# SSFocuser-B-DRV8825.net
KiCad netlist of a schematic drawn in Altium Designer
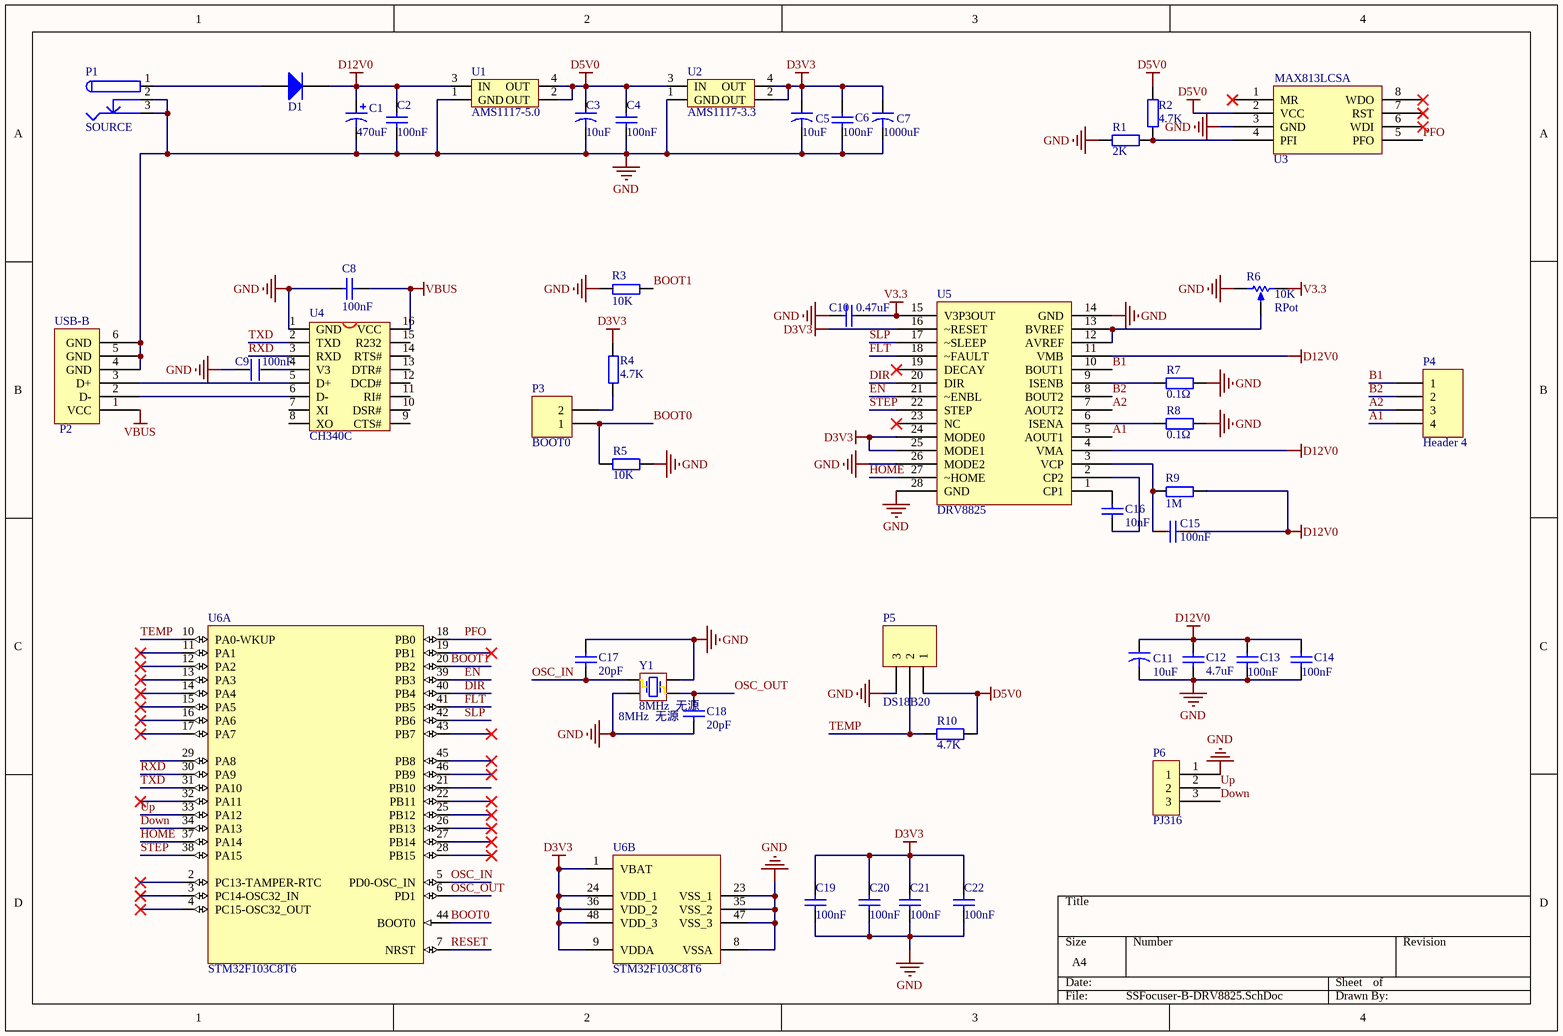
[diagram p0: SSFocuser-B-DRV8825.SchDoc]

(export (version "E")
  (design (tool "Eeschema 10.0.6"))
  (components
    (comp (ref "C1")
      (value "470uF")
      (footprint "16V/470U(CD10X10D5)")
      (description "470UF      16V      CD10X10D5")
      (libsource (lib "平台原理图symbol图库V1.0") (part "C470UF016S"))
    )
    (comp (ref "C2")
      (value "100nF")
      (footprint "0603C")
      (description "Capacitor")
      (fields (field (name "PUBLISHER") "Altium Limited"))
      (libsource (lib "Crazy_PCB") (part "Cap"))
    )
    (comp (ref "C3")
      (value "10uF")
      (footprint "3216")
      (fields (field (name "VAULE") "10uF"))
      (libsource (lib "Crazy_PCB") (part "CAP2"))
    )
    (comp (ref "C4")
      (value "100nF")
      (footprint "0603C")
      (description "Capacitor")
      (fields (field (name "PUBLISHER") "Altium Limited"))
      (libsource (lib "Crazy_PCB") (part "Cap"))
    )
    (comp (ref "C5")
      (value "10uF")
      (footprint "3216")
      (fields (field (name "VAULE") "10uF"))
      (libsource (lib "Crazy_PCB") (part "CAP2"))
    )
    (comp (ref "C6")
      (value "100nF")
      (footprint "0603C")
      (description "Capacitor")
      (fields (field (name "PUBLISHER") "Altium Limited"))
      (libsource (lib "Crazy_PCB") (part "Cap"))
    )
    (comp (ref "C7")
      (value "1000uF")
      (footprint "16V/470U(CD10X10D5)")
      (fields (field (name "VAULE") "1000uF"))
      (libsource (lib "Crazy_PCB") (part "CAP2"))
    )
    (comp (ref "C8")
      (value "100nF")
      (footprint "0603C")
      (description "Capacitor")
      (fields (field (name "PUBLISHER") "Altium Limited"))
      (libsource (lib "Crazy_PCB") (part "Cap"))
    )
    (comp (ref "C9")
      (value "100nF")
      (footprint "0603C")
      (libsource (lib "WarShip V3 STM32103封装库") (part "C"))
    )
    (comp (ref "C10")
      (value "0.47uF")
      (footprint "0603C")
      (description "Capacitor")
      (fields (field (name "PUBLISHER") "Altium Limited"))
      (libsource (lib "Crazy_PCB") (part "Cap"))
    )
    (comp (ref "C11")
      (value "10uF")
      (footprint "3216")
      (fields (field (name "VAULE") "10uF"))
      (libsource (lib "Crazy_PCB") (part "CAP2"))
    )
    (comp (ref "C12")
      (value "4.7uF")
      (footprint "1206C")
      (description "Capacitor")
      (fields (field (name "PUBLISHER") "Altium Limited"))
      (libsource (lib "Crazy_PCB") (part "Cap"))
    )
    (comp (ref "C13")
      (value "100nF")
      (footprint "0603C")
      (description "Capacitor")
      (fields (field (name "PUBLISHER") "Altium Limited"))
      (libsource (lib "Crazy_PCB") (part "Cap"))
    )
    (comp (ref "C14")
      (value "100nF")
      (footprint "0603C")
      (description "Capacitor")
      (fields (field (name "PUBLISHER") "Altium Limited"))
      (libsource (lib "Crazy_PCB") (part "Cap"))
    )
    (comp (ref "C15")
      (value "100nF")
      (footprint "0603C")
      (description "Capacitor")
      (fields (field (name "PUBLISHER") "Altium Limited"))
      (libsource (lib "Crazy_PCB") (part "Cap"))
    )
    (comp (ref "C16")
      (value "10nF")
      (footprint "0603C")
      (description "Capacitor")
      (fields (field (name "PUBLISHER") "Altium Limited"))
      (libsource (lib "Crazy_PCB") (part "Cap"))
    )
    (comp (ref "C17")
      (value "20pF")
      (footprint "0603C")
      (description "Capacitor")
      (fields (field (name "PUBLISHER") "Altium Limited"))
      (libsource (lib "JL_SCH") (part "Cap"))
    )
    (comp (ref "C18")
      (value "20pF")
      (footprint "0603C")
      (description "Capacitor")
      (fields (field (name "PUBLISHER") "Altium Limited"))
      (libsource (lib "JL_SCH") (part "Cap"))
    )
    (comp (ref "C19")
      (value "100nF")
      (footprint "0603C")
      (description "Capacitor")
      (fields (field (name "PUBLISHER") "Altium Limited"))
      (libsource (lib "Crazy_PCB") (part "Cap"))
    )
    (comp (ref "C20")
      (value "100nF")
      (footprint "0603C")
      (description "Capacitor")
      (fields (field (name "PUBLISHER") "Altium Limited"))
      (libsource (lib "Crazy_PCB") (part "Cap"))
    )
    (comp (ref "C21")
      (value "100nF")
      (footprint "0603C")
      (description "Capacitor")
      (fields (field (name "PUBLISHER") "Altium Limited"))
      (libsource (lib "Crazy_PCB") (part "Cap"))
    )
    (comp (ref "C22")
      (value "100nF")
      (footprint "0603C")
      (description "Capacitor")
      (fields (field (name "PUBLISHER") "Altium Limited"))
      (libsource (lib "Crazy_PCB") (part "Cap"))
    )
    (comp (ref "D1")
      (value "M7")
      (footprint "DO-214AC")
      (description "High Conductance Fast Diode")
      (fields (field (name "PUBLISHER") "Altium Limited"))
      (libsource (lib "Crazy_PCB") (part "Diode"))
    )
    (comp (ref "P1")
      (value "SOURCE")
      (footprint "DC_5.5MM")
      (fields (field (name "PUBLISHER") "Altium Limited"))
      (libsource (lib "Crazy_PCB") (part "SOURCE"))
    )
    (comp (ref "P2") (value "USB-B") (footprint "USB-B") (libsource (lib "DX") (part "USB-B")))
    (comp (ref "P3")
      (value "BOOT0")
      (footprint "HDR1X2")
      (description "Header, 2-Pin")
      (fields (field (name "PUBLISHER") "Altium Limited"))
      (libsource (lib "Miscellaneous Connectors") (part "MHDR1X2"))
    )
    (comp (ref "P4")
      (value "Header 4")
      (footprint "XH_4_V")
      (description "Header, 4-Pin")
      (fields (field (name "PUBLISHER") "Altium Limited"))
      (libsource (lib "Miscellaneous Connectors") (part "Header 4"))
    )
    (comp (ref "P5")
      (value "DS18B20")
      (footprint "TO-92B")
      (description "Header, 3-Pin")
      (fields (field (name "PUBLISHER") "Altium Limited"))
      (libsource (lib "Miscellaneous Connectors") (part "Header 3"))
    )
    (comp (ref "P6") (value "PJ316") (footprint "PJ316") (libsource (lib "SS") (part "PJ316")))
    (comp (ref "R1")
      (value "2K")
      (footprint "0603R")
      (description "Resistor")
      (fields (field (name "PUBLISHER") "Altium Limited"))
      (libsource (lib "Crazy_PCB") (part "RES"))
    )
    (comp (ref "R2")
      (value "4.7K")
      (footprint "0603R")
      (description "Resistor")
      (fields (field (name "PUBLISHER") "Altium Limited"))
      (libsource (lib "") (part "RES_2"))
    )
    (comp (ref "R3") (value "10K") (footprint "0603R") (libsource (lib "WarShip V3 STM32103封装库") (part "R")))
    (comp (ref "R4") (value "4.7K") (footprint "0603R") (libsource (lib "WarShip V3 STM32103封装库") (part "R")))
    (comp (ref "R5")
      (value "10K")
      (footprint "0603R")
      (description "Resistor")
      (fields (field (name "PUBLISHER") "Altium Limited"))
      (libsource (lib "") (part "RES_1"))
    )
    (comp (ref "R6")
      (value "RPot")
      (footprint "VR_SMD")
      (description "Potentiometer")
      (fields (field (name "ALTIUM_VALUE") "10K") (field (name "PUBLISHER") "Altium Limited"))
      (libsource (lib "Miscellaneous Devices") (part "RPot"))
    )
    (comp (ref "R7")
      (value "0.1Ω")
      (footprint "1206R")
      (description "Resistor")
      (fields (field (name "PUBLISHER") "Altium Limited"))
      (libsource (lib "Crazy_PCB") (part "RES"))
    )
    (comp (ref "R8")
      (value "0.1Ω")
      (footprint "1206R")
      (description "Resistor")
      (fields (field (name "PUBLISHER") "Altium Limited"))
      (libsource (lib "Crazy_PCB") (part "RES"))
    )
    (comp (ref "R9") (value "1M") (footprint "0603R") (libsource (lib "WarShip V3 STM32103封装库") (part "R")))
    (comp (ref "R10")
      (value "4.7K")
      (footprint "0603R")
      (description "Resistor")
      (fields (field (name "PUBLISHER") "Altium Limited"))
      (libsource (lib "") (part "RES_1"))
    )
    (comp (ref "U1")
      (value "AMS1117-5.0")
      (footprint "SOT223")
      (libsource (lib "MiniSTM32 V3.0封装库") (part "AMS1117"))
    )
    (comp (ref "U2")
      (value "AMS1117-3.3")
      (footprint "SOT223")
      (libsource (lib "MiniSTM32 V3.0封装库") (part "AMS1117"))
    )
    (comp (ref "U3") (value "MAX813LCSA") (footprint "SOP-8") (libsource (lib "DX") (part "MAX813L")))
    (comp (ref "U4")
      (value "CH340C")
      (footprint "SO-16")
      (description "USB2UART")
      (libsource (lib "WarShip V3 STM32103封装库") (part "CH340G"))
    )
    (comp (ref "U5") (value "DRV8825") (footprint "HTSSOP") (libsource (lib "MySchlib") (part "DRV8825")))
    (comp (ref "U6")
      (value "STM32F103C8T6")
      (footprint "LQFP48_N")
      (libsource (lib "STMicroelectronics STM32 F1") (part "STM32F103C8T6"))
    )
    (comp (ref "Y1")
      (value "8MHz  无源")
      (footprint "X3225")
      (description "Crystal Oscillator")
      (fields (field (name "ALTIUM_VALUE") "8MHz  无源") (field (name "PUBLISHER") "Altium Limited"))
      (libsource (lib "JL_SCH") (part "XTAL_1"))
    )
  )
  (nets
    (net (code "1") (name "/A1") (class "Default")
      (node (ref "P4") (pin "4") (pinfunction "4_4") (pintype "passive"))
      (node (ref "U5") (pin "5") (pinfunction "AOUT1_5") (pintype "passive"))
    )
    (net (code "2") (name "/A2") (class "Default")
      (node (ref "P4") (pin "3") (pinfunction "3_3") (pintype "passive"))
      (node (ref "U5") (pin "7") (pinfunction "AOUT2_7") (pintype "passive"))
    )
    (net (code "3") (name "/B1") (class "Default")
      (node (ref "P4") (pin "1") (pinfunction "1_1") (pintype "passive"))
      (node (ref "U5") (pin "10") (pinfunction "BOUT1_10") (pintype "passive"))
    )
    (net (code "4") (name "/B2") (class "Default")
      (node (ref "P4") (pin "2") (pinfunction "2_2") (pintype "passive"))
      (node (ref "U5") (pin "8") (pinfunction "BOUT2_8") (pintype "passive"))
    )
    (net (code "5") (name "/BOOT0") (class "Default")
      (node (ref "P3") (pin "1") (pinfunction "1_1") (pintype "passive"))
      (node (ref "R5") (pin "1") (pinfunction "1_1") (pintype "passive"))
      (node (ref "U6") (pin "44") (pinfunction "BOOT0_44") (pintype "input"))
    )
    (net (code "6") (name "/BOOT1") (class "Default")
      (node (ref "R3") (pin "2") (pintype "passive"))
      (node (ref "U6") (pin "20") (pinfunction "PB2_20") (pintype "bidirectional"))
    )
    (net (code "7") (name "/DIR") (class "Default")
      (node (ref "U5") (pin "20") (pinfunction "DIR_20") (pintype "passive"))
      (node (ref "U6") (pin "40") (pinfunction "PB4_40") (pintype "bidirectional"))
    )
    (net (code "8") (name "/Down") (class "Default")
      (node (ref "P6") (pin "3") (pinfunction "3_3") (pintype "passive"))
      (node (ref "U6") (pin "34") (pinfunction "PA13_34") (pintype "bidirectional"))
    )
    (net (code "9") (name "/EN") (class "Default")
      (node (ref "U5") (pin "21") (pinfunction "~ENBL_21") (pintype "passive"))
      (node (ref "U6") (pin "39") (pinfunction "PB3_39") (pintype "bidirectional"))
    )
    (net (code "10") (name "/FLT") (class "Default")
      (node (ref "U5") (pin "18") (pinfunction "~FAULT_18") (pintype "passive"))
      (node (ref "U6") (pin "41") (pinfunction "PB5_41") (pintype "bidirectional"))
    )
    (net (code "11") (name "/HOME") (class "Default")
      (node (ref "U5") (pin "27") (pinfunction "~HOME_27") (pintype "passive"))
      (node (ref "U6") (pin "37") (pinfunction "PA14_37") (pintype "bidirectional"))
    )
    (net (code "12") (name "/OSC_IN") (class "Default")
      (node (ref "C17") (pin "1") (pinfunction "1_1") (pintype "passive"))
      (node (ref "U6") (pin "5") (pinfunction "PD0-OSC_IN_5") (pintype "bidirectional"))
      (node (ref "Y1") (pin "1") (pinfunction "OSC1_1") (pintype "passive"))
    )
    (net (code "13") (name "/OSC_OUT") (class "Default")
      (node (ref "C18") (pin "1") (pinfunction "1_1") (pintype "passive"))
      (node (ref "U6") (pin "6") (pinfunction "PD1_6") (pintype "bidirectional"))
      (node (ref "Y1") (pin "3") (pinfunction "OSC2_3") (pintype "passive"))
    )
    (net (code "14") (name "/PFO") (class "Default")
      (node (ref "U3") (pin "5") (pinfunction "PFO_5") (pintype "passive"))
      (node (ref "U6") (pin "18") (pinfunction "PB0_18") (pintype "bidirectional"))
    )
    (net (code "15") (name "/RESET") (class "Default")
      (node (ref "U6") (pin "7") (pinfunction "NRST_7") (pintype "bidirectional"))
    )
    (net (code "16") (name "/RXD") (class "Default")
      (node (ref "U4") (pin "3") (pinfunction "RXD_3") (pintype "passive"))
      (node (ref "U6") (pin "30") (pinfunction "PA9_30") (pintype "bidirectional"))
    )
    (net (code "17") (name "/SLP") (class "Default")
      (node (ref "U5") (pin "17") (pinfunction "~SLEEP_17") (pintype "passive"))
      (node (ref "U6") (pin "42") (pinfunction "PB6_42") (pintype "bidirectional"))
    )
    (net (code "18") (name "/STEP") (class "Default")
      (node (ref "U5") (pin "22") (pinfunction "STEP_22") (pintype "passive"))
      (node (ref "U6") (pin "38") (pinfunction "PA15_38") (pintype "bidirectional"))
    )
    (net (code "19") (name "/TEMP") (class "Default")
      (node (ref "P5") (pin "2") (pinfunction "2_2") (pintype "passive"))
      (node (ref "R10") (pin "1") (pinfunction "1_1") (pintype "passive"))
      (node (ref "U6") (pin "10") (pinfunction "PA0-WKUP_10") (pintype "bidirectional"))
    )
    (net (code "20") (name "/TXD") (class "Default")
      (node (ref "U4") (pin "2") (pinfunction "TXD_2") (pintype "passive"))
      (node (ref "U6") (pin "31") (pinfunction "PA10_31") (pintype "bidirectional"))
    )
    (net (code "21") (name "/Up") (class "Default")
      (node (ref "P6") (pin "2") (pinfunction "2_2") (pintype "passive"))
      (node (ref "U6") (pin "33") (pinfunction "PA12_33") (pintype "bidirectional"))
    )
    (net (code "22") (name "D3V3") (class "Default")
      (node (ref "C19") (pin "2") (pinfunction "2_2") (pintype "passive"))
      (node (ref "C20") (pin "2") (pinfunction "2_2") (pintype "passive"))
      (node (ref "C21") (pin "2") (pinfunction "2_2") (pintype "passive"))
      (node (ref "C22") (pin "2") (pinfunction "2_2") (pintype "passive"))
      (node (ref "C5") (pin "1") (pinfunction "1_1") (pintype "passive"))
      (node (ref "C6") (pin "2") (pinfunction "2_2") (pintype "passive"))
      (node (ref "C7") (pin "1") (pinfunction "1_1") (pintype "passive"))
      (node (ref "R4") (pin "2") (pintype "passive"))
      (node (ref "U2") (pin "2") (pinfunction "OUT_2") (pintype "passive"))
      (node (ref "U2") (pin "4") (pinfunction "OUT_4") (pintype "passive"))
      (node (ref "U5") (pin "16") (pinfunction "~RESET_16") (pintype "passive"))
      (node (ref "U5") (pin "24") (pinfunction "MODE0_24") (pintype "passive"))
      (node (ref "U5") (pin "25") (pinfunction "MODE1_25") (pintype "passive"))
      (node (ref "U6") (pin "1") (pinfunction "VBAT_1") (pintype "power_in"))
      (node (ref "U6") (pin "24") (pinfunction "VDD_1_24") (pintype "power_in"))
      (node (ref "U6") (pin "36") (pinfunction "VDD_2_36") (pintype "power_in"))
      (node (ref "U6") (pin "48") (pinfunction "VDD_3_48") (pintype "power_in"))
      (node (ref "U6") (pin "9") (pinfunction "VDDA_9") (pintype "power_in"))
    )
    (net (code "23") (name "D5V0") (class "Default")
      (node (ref "C3") (pin "1") (pinfunction "1_1") (pintype "passive"))
      (node (ref "C4") (pin "2") (pinfunction "2_2") (pintype "passive"))
      (node (ref "P5") (pin "1") (pinfunction "1_1") (pintype "passive"))
      (node (ref "R10") (pin "2") (pinfunction "2_2") (pintype "passive"))
      (node (ref "R2") (pin "2") (pinfunction "2_2") (pintype "passive"))
      (node (ref "U1") (pin "2") (pinfunction "OUT_2") (pintype "passive"))
      (node (ref "U1") (pin "4") (pinfunction "OUT_4") (pintype "passive"))
      (node (ref "U2") (pin "3") (pinfunction "IN_3") (pintype "passive"))
      (node (ref "U3") (pin "2") (pinfunction "VCC_2") (pintype "passive"))
    )
    (net (code "24") (name "D12V0") (class "Default")
      (node (ref "C1") (pin "1") (pinfunction "1_1") (pintype "passive"))
      (node (ref "C11") (pin "1") (pinfunction "1_1") (pintype "passive"))
      (node (ref "C12") (pin "1") (pinfunction "1_1") (pintype "passive"))
      (node (ref "C13") (pin "2") (pinfunction "2_2") (pintype "passive"))
      (node (ref "C14") (pin "2") (pinfunction "2_2") (pintype "passive"))
      (node (ref "C15") (pin "1") (pinfunction "1_1") (pintype "passive"))
      (node (ref "C2") (pin "2") (pinfunction "2_2") (pintype "passive"))
      (node (ref "D1") (pin "2") (pinfunction "K_2") (pintype "passive"))
      (node (ref "R9") (pin "2") (pintype "passive"))
      (node (ref "U1") (pin "3") (pinfunction "IN_3") (pintype "passive"))
      (node (ref "U5") (pin "11") (pinfunction "VMB_11") (pintype "passive"))
      (node (ref "U5") (pin "4") (pinfunction "VMA_4") (pintype "passive"))
    )
    (net (code "25") (name "GND") (class "Default")
      (node (ref "C1") (pin "2") (pinfunction "2_2") (pintype "passive"))
      (node (ref "C10") (pin "1") (pinfunction "1_1") (pintype "passive"))
      (node (ref "C11") (pin "2") (pinfunction "2_2") (pintype "passive"))
      (node (ref "C12") (pin "2") (pinfunction "2_2") (pintype "passive"))
      (node (ref "C13") (pin "1") (pinfunction "1_1") (pintype "passive"))
      (node (ref "C14") (pin "1") (pinfunction "1_1") (pintype "passive"))
      (node (ref "C17") (pin "2") (pinfunction "2_2") (pintype "passive"))
      (node (ref "C18") (pin "2") (pinfunction "2_2") (pintype "passive"))
      (node (ref "C19") (pin "1") (pinfunction "1_1") (pintype "passive"))
      (node (ref "C2") (pin "1") (pinfunction "1_1") (pintype "passive"))
      (node (ref "C20") (pin "1") (pinfunction "1_1") (pintype "passive"))
      (node (ref "C21") (pin "1") (pinfunction "1_1") (pintype "passive"))
      (node (ref "C22") (pin "1") (pinfunction "1_1") (pintype "passive"))
      (node (ref "C3") (pin "2") (pinfunction "2_2") (pintype "passive"))
      (node (ref "C4") (pin "1") (pinfunction "1_1") (pintype "passive"))
      (node (ref "C5") (pin "2") (pinfunction "2_2") (pintype "passive"))
      (node (ref "C6") (pin "1") (pinfunction "1_1") (pintype "passive"))
      (node (ref "C7") (pin "2") (pinfunction "2_2") (pintype "passive"))
      (node (ref "C8") (pin "1") (pinfunction "1_1") (pintype "passive"))
      (node (ref "C9") (pin "1") (pintype "passive"))
      (node (ref "P1") (pin "2") (pinfunction "2_2") (pintype "power_in"))
      (node (ref "P1") (pin "3") (pinfunction "3_3") (pintype "power_in"))
      (node (ref "P2") (pin "4") (pinfunction "GND_4") (pintype "passive"))
      (node (ref "P2") (pin "5") (pinfunction "GND_5") (pintype "passive"))
      (node (ref "P2") (pin "6") (pinfunction "GND_6") (pintype "passive"))
      (node (ref "P5") (pin "3") (pinfunction "3_3") (pintype "passive"))
      (node (ref "P6") (pin "1") (pinfunction "1_1") (pintype "passive"))
      (node (ref "R1") (pin "2") (pinfunction "2_2") (pintype "passive"))
      (node (ref "R3") (pin "1") (pintype "passive"))
      (node (ref "R5") (pin "2") (pinfunction "2_2") (pintype "passive"))
      (node (ref "R6") (pin "1") (pinfunction "TOP_1") (pintype "passive"))
      (node (ref "R7") (pin "1") (pinfunction "1_1") (pintype "passive"))
      (node (ref "R8") (pin "1") (pinfunction "1_1") (pintype "passive"))
      (node (ref "U1") (pin "1") (pinfunction "GND_1") (pintype "passive"))
      (node (ref "U2") (pin "1") (pinfunction "GND_1") (pintype "passive"))
      (node (ref "U3") (pin "3") (pinfunction "GND_3") (pintype "passive"))
      (node (ref "U4") (pin "1") (pinfunction "GND_1") (pintype "passive"))
      (node (ref "U5") (pin "14") (pinfunction "GND_14") (pintype "passive"))
      (node (ref "U5") (pin "26") (pinfunction "MODE2_26") (pintype "passive"))
      (node (ref "U5") (pin "28") (pinfunction "GND_28") (pintype "passive"))
      (node (ref "U6") (pin "23") (pinfunction "VSS_1_23") (pintype "power_in"))
      (node (ref "U6") (pin "35") (pinfunction "VSS_2_35") (pintype "power_in"))
      (node (ref "U6") (pin "47") (pinfunction "VSS_3_47") (pintype "power_in"))
      (node (ref "U6") (pin "8") (pinfunction "VSSA_8") (pintype "power_in"))
      (node (ref "Y1") (pin "2") (pinfunction "NA_2") (pintype "passive"))
      (node (ref "Y1") (pin "4") (pinfunction "NA_4") (pintype "passive"))
    )
    (net (code "26") (name "Net-(D1-A)") (class "Default")
      (node (ref "D1") (pin "1") (pinfunction "A_1") (pintype "passive"))
      (node (ref "P1") (pin "1") (pinfunction "1_1") (pintype "power_in"))
    )
    (net (code "27") (name "Net-(P2-D+)") (class "Default")
      (node (ref "P2") (pin "3") (pinfunction "D+_3") (pintype "passive"))
      (node (ref "U4") (pin "5") (pinfunction "D+_5") (pintype "passive"))
    )
    (net (code "28") (name "Net-(P2-D-)") (class "Default")
      (node (ref "P2") (pin "2") (pinfunction "D-_2") (pintype "passive"))
      (node (ref "U4") (pin "6") (pinfunction "D-_6") (pintype "passive"))
    )
    (net (code "29") (name "Net-(P3-Pad2)") (class "Default")
      (node (ref "P3") (pin "2") (pinfunction "2_2") (pintype "passive"))
      (node (ref "R4") (pin "1") (pintype "passive"))
    )
    (net (code "30") (name "Net-(R6-TAP)") (class "Default")
      (node (ref "R6") (pin "3") (pinfunction "TAP_3") (pintype "passive"))
      (node (ref "U5") (pin "12") (pinfunction "AVREF_12") (pintype "passive"))
      (node (ref "U5") (pin "13") (pinfunction "BVREF_13") (pintype "passive"))
    )
    (net (code "31") (name "Net-(U3-PFI)") (class "Default")
      (node (ref "R1") (pin "1") (pinfunction "1_1") (pintype "passive"))
      (node (ref "R2") (pin "1") (pinfunction "1_1") (pintype "passive"))
      (node (ref "U3") (pin "4") (pinfunction "PFI_4") (pintype "passive"))
    )
    (net (code "32") (name "Net-(U4-V3)") (class "Default")
      (node (ref "C9") (pin "2") (pintype "passive"))
      (node (ref "U4") (pin "4") (pinfunction "V3_4") (pintype "passive"))
    )
    (net (code "33") (name "Net-(U5-CP1)") (class "Default")
      (node (ref "C16") (pin "2") (pinfunction "2_2") (pintype "passive"))
      (node (ref "U5") (pin "1") (pinfunction "CP1_1") (pintype "passive"))
    )
    (net (code "34") (name "Net-(U5-CP2)") (class "Default")
      (node (ref "C16") (pin "1") (pinfunction "1_1") (pintype "passive"))
      (node (ref "U5") (pin "2") (pinfunction "CP2_2") (pintype "passive"))
    )
    (net (code "35") (name "Net-(U5-ISENA)") (class "Default")
      (node (ref "R8") (pin "2") (pinfunction "2_2") (pintype "passive"))
      (node (ref "U5") (pin "6") (pinfunction "ISENA_6") (pintype "passive"))
    )
    (net (code "36") (name "Net-(U5-ISENB)") (class "Default")
      (node (ref "R7") (pin "2") (pinfunction "2_2") (pintype "passive"))
      (node (ref "U5") (pin "9") (pinfunction "ISENB_9") (pintype "passive"))
    )
    (net (code "37") (name "Net-(U5-VCP)") (class "Default")
      (node (ref "C15") (pin "2") (pinfunction "2_2") (pintype "passive"))
      (node (ref "R9") (pin "1") (pintype "passive"))
      (node (ref "U5") (pin "3") (pinfunction "VCP_3") (pintype "passive"))
    )
    (net (code "38") (name "V3.3") (class "Default")
      (node (ref "C10") (pin "2") (pinfunction "2_2") (pintype "passive"))
      (node (ref "R6") (pin "2") (pinfunction "BOT_2") (pintype "passive"))
      (node (ref "U5") (pin "15") (pinfunction "V3P3OUT_15") (pintype "passive"))
    )
    (net (code "39") (name "VBUS") (class "Default")
      (node (ref "C8") (pin "2") (pinfunction "2_2") (pintype "passive"))
      (node (ref "P2") (pin "1") (pinfunction "VCC_1") (pintype "passive"))
      (node (ref "U4") (pin "16") (pinfunction "VCC_16") (pintype "passive"))
    )
    (net (code "40") (name "unconnected-(U3-MR-Pad1)") (class "Default")
      (node (ref "U3") (pin "1") (pinfunction "MR_1") (pintype "passive+no_connect"))
    )
    (net (code "41") (name "unconnected-(U3-RST-Pad7)") (class "Default")
      (node (ref "U3") (pin "7") (pinfunction "RST_7") (pintype "passive+no_connect"))
    )
    (net (code "42") (name "unconnected-(U3-WDI-Pad6)") (class "Default")
      (node (ref "U3") (pin "6") (pinfunction "WDI_6") (pintype "passive+no_connect"))
    )
    (net (code "43") (name "unconnected-(U3-WDO-Pad8)") (class "Default")
      (node (ref "U3") (pin "8") (pinfunction "WDO_8") (pintype "passive+no_connect"))
    )
    (net (code "44") (name "unconnected-(U4-CTS#-Pad9)") (class "Default")
      (node (ref "U4") (pin "9") (pinfunction "CTS#_9") (pintype "passive"))
    )
    (net (code "45") (name "unconnected-(U4-DCD#-Pad12)") (class "Default")
      (node (ref "U4") (pin "12") (pinfunction "DCD#_12") (pintype "passive"))
    )
    (net (code "46") (name "unconnected-(U4-DSR#-Pad10)") (class "Default")
      (node (ref "U4") (pin "10") (pinfunction "DSR#_10") (pintype "passive"))
    )
    (net (code "47") (name "unconnected-(U4-DTR#-Pad13)") (class "Default")
      (node (ref "U4") (pin "13") (pinfunction "DTR#_13") (pintype "passive"))
    )
    (net (code "48") (name "unconnected-(U4-R232-Pad15)") (class "Default")
      (node (ref "U4") (pin "15") (pinfunction "R232_15") (pintype "passive"))
    )
    (net (code "49") (name "unconnected-(U4-RI#-Pad11)") (class "Default")
      (node (ref "U4") (pin "11") (pinfunction "RI#_11") (pintype "passive"))
    )
    (net (code "50") (name "unconnected-(U4-RTS#-Pad14)") (class "Default")
      (node (ref "U4") (pin "14") (pinfunction "RTS#_14") (pintype "passive"))
    )
    (net (code "51") (name "unconnected-(U4-XI-Pad7)") (class "Default")
      (node (ref "U4") (pin "7") (pinfunction "XI_7") (pintype "passive"))
    )
    (net (code "52") (name "unconnected-(U4-XO-Pad8)") (class "Default")
      (node (ref "U4") (pin "8") (pinfunction "XO_8") (pintype "passive"))
    )
    (net (code "53") (name "unconnected-(U5-DECAY-Pad19)") (class "Default")
      (node (ref "U5") (pin "19") (pinfunction "DECAY_19") (pintype "passive+no_connect"))
    )
    (net (code "54") (name "unconnected-(U5-NC-Pad23)") (class "Default")
      (node (ref "U5") (pin "23") (pinfunction "NC_23") (pintype "passive+no_connect"))
    )
    (net (code "55") (name "unconnected-(U6A-PA1-Pad11)") (class "Default")
      (node (ref "U6") (pin "11") (pinfunction "PA1_11") (pintype "bidirectional+no_connect"))
    )
    (net (code "56") (name "unconnected-(U6A-PA2-Pad12)") (class "Default")
      (node (ref "U6") (pin "12") (pinfunction "PA2_12") (pintype "bidirectional+no_connect"))
    )
    (net (code "57") (name "unconnected-(U6A-PA3-Pad13)") (class "Default")
      (node (ref "U6") (pin "13") (pinfunction "PA3_13") (pintype "bidirectional+no_connect"))
    )
    (net (code "58") (name "unconnected-(U6A-PA4-Pad14)") (class "Default")
      (node (ref "U6") (pin "14") (pinfunction "PA4_14") (pintype "bidirectional+no_connect"))
    )
    (net (code "59") (name "unconnected-(U6A-PA5-Pad15)") (class "Default")
      (node (ref "U6") (pin "15") (pinfunction "PA5_15") (pintype "bidirectional+no_connect"))
    )
    (net (code "60") (name "unconnected-(U6A-PA6-Pad16)") (class "Default")
      (node (ref "U6") (pin "16") (pinfunction "PA6_16") (pintype "bidirectional+no_connect"))
    )
    (net (code "61") (name "unconnected-(U6A-PA7-Pad17)") (class "Default")
      (node (ref "U6") (pin "17") (pinfunction "PA7_17") (pintype "bidirectional+no_connect"))
    )
    (net (code "62") (name "unconnected-(U6A-PA8-Pad29)") (class "Default")
      (node (ref "U6") (pin "29") (pinfunction "PA8_29") (pintype "bidirectional"))
    )
    (net (code "63") (name "unconnected-(U6A-PA11-Pad32)") (class "Default")
      (node (ref "U6") (pin "32") (pinfunction "PA11_32") (pintype "bidirectional+no_connect"))
    )
    (net (code "64") (name "unconnected-(U6A-PB1-Pad19)") (class "Default")
      (node (ref "U6") (pin "19") (pinfunction "PB1_19") (pintype "bidirectional+no_connect"))
    )
    (net (code "65") (name "unconnected-(U6A-PB7-Pad43)") (class "Default")
      (node (ref "U6") (pin "43") (pinfunction "PB7_43") (pintype "bidirectional+no_connect"))
    )
    (net (code "66") (name "unconnected-(U6A-PB8-Pad45)") (class "Default")
      (node (ref "U6") (pin "45") (pinfunction "PB8_45") (pintype "bidirectional+no_connect"))
    )
    (net (code "67") (name "unconnected-(U6A-PB9-Pad46)") (class "Default")
      (node (ref "U6") (pin "46") (pinfunction "PB9_46") (pintype "bidirectional+no_connect"))
    )
    (net (code "68") (name "unconnected-(U6A-PB10-Pad21)") (class "Default")
      (node (ref "U6") (pin "21") (pinfunction "PB10_21") (pintype "bidirectional"))
    )
    (net (code "69") (name "unconnected-(U6A-PB11-Pad22)") (class "Default")
      (node (ref "U6") (pin "22") (pinfunction "PB11_22") (pintype "bidirectional+no_connect"))
    )
    (net (code "70") (name "unconnected-(U6A-PB12-Pad25)") (class "Default")
      (node (ref "U6") (pin "25") (pinfunction "PB12_25") (pintype "bidirectional+no_connect"))
    )
    (net (code "71") (name "unconnected-(U6A-PB13-Pad26)") (class "Default")
      (node (ref "U6") (pin "26") (pinfunction "PB13_26") (pintype "bidirectional+no_connect"))
    )
    (net (code "72") (name "unconnected-(U6A-PB14-Pad27)") (class "Default")
      (node (ref "U6") (pin "27") (pinfunction "PB14_27") (pintype "bidirectional+no_connect"))
    )
    (net (code "73") (name "unconnected-(U6A-PB15-Pad28)") (class "Default")
      (node (ref "U6") (pin "28") (pinfunction "PB15_28") (pintype "bidirectional+no_connect"))
    )
    (net (code "74") (name "unconnected-(U6A-PC13-TAMPER-RTC-Pad2)") (class "Default")
      (node (ref "U6") (pin "2") (pinfunction "PC13-TAMPER-RTC_2") (pintype "bidirectional+no_connect"))
    )
    (net (code "75") (name "unconnected-(U6A-PC14-OSC32_IN-Pad3)") (class "Default")
      (node (ref "U6") (pin "3") (pinfunction "PC14-OSC32_IN_3") (pintype "bidirectional+no_connect"))
    )
    (net (code "76") (name "unconnected-(U6A-PC15-OSC32_OUT-Pad4)") (class "Default")
      (node (ref "U6") (pin "4") (pinfunction "PC15-OSC32_OUT_4") (pintype "bidirectional+no_connect"))
    )
  )
)
